# improved_sample-and-hold-cpy.net
KiCad netlist of a schematic drawn in EAGLE
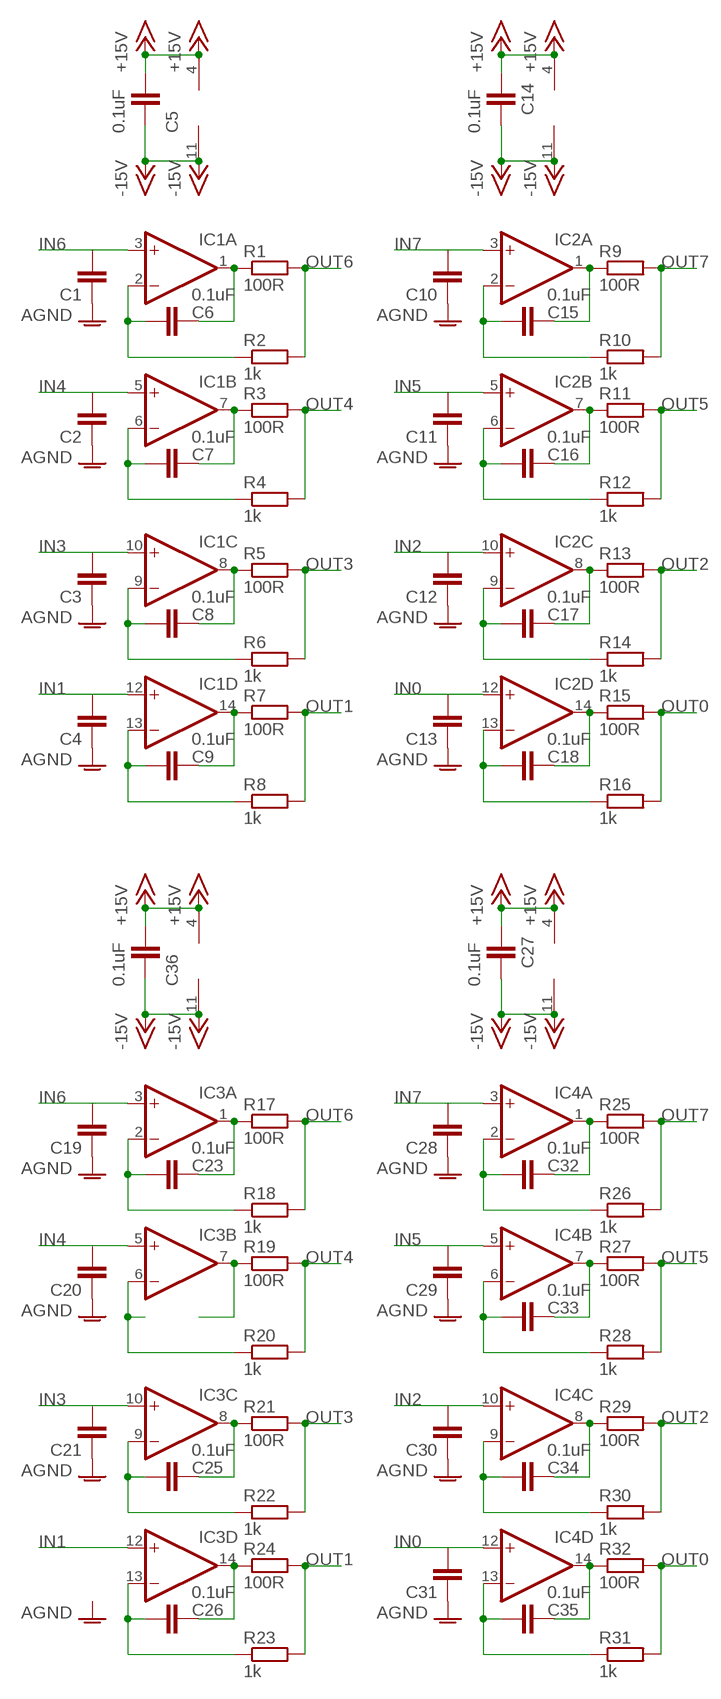
[diagram p0: schematic, sheet 1]

(export (version "E")
  (design (tool "Eeschema 10.0.6"))
  (components
    (comp (ref "C1")
      (value "C-EUC1206")
      (footprint "eagle-import:C1206")
      (libsource (lib "eagle-import") (part "C-EUC1206"))
    )
    (comp (ref "C2")
      (value "C-EUC1206")
      (footprint "eagle-import:C1206")
      (libsource (lib "eagle-import") (part "C-EUC1206"))
    )
    (comp (ref "C3")
      (value "C-EUC1206")
      (footprint "eagle-import:C1206")
      (libsource (lib "eagle-import") (part "C-EUC1206"))
    )
    (comp (ref "C4")
      (value "C-EUC1206")
      (footprint "eagle-import:C1206")
      (libsource (lib "eagle-import") (part "C-EUC1206"))
    )
    (comp (ref "C5")
      (value "0.1uF")
      (footprint "eagle-import:C0603")
      (libsource (lib "eagle-import") (part "C-EUC0603"))
    )
    (comp (ref "C6")
      (value "0.1uF")
      (footprint "eagle-import:C0603")
      (libsource (lib "eagle-import") (part "C-EUC0603"))
    )
    (comp (ref "C7")
      (value "0.1uF")
      (footprint "eagle-import:C0603")
      (libsource (lib "eagle-import") (part "C-EUC0603"))
    )
    (comp (ref "C8")
      (value "0.1uF")
      (footprint "eagle-import:C0603")
      (libsource (lib "eagle-import") (part "C-EUC0603"))
    )
    (comp (ref "C9")
      (value "0.1uF")
      (footprint "eagle-import:C0603")
      (libsource (lib "eagle-import") (part "C-EUC0603"))
    )
    (comp (ref "C10")
      (value "C-EUC1206")
      (footprint "eagle-import:C1206")
      (libsource (lib "eagle-import") (part "C-EUC1206"))
    )
    (comp (ref "C11")
      (value "C-EUC1206")
      (footprint "eagle-import:C1206")
      (libsource (lib "eagle-import") (part "C-EUC1206"))
    )
    (comp (ref "C12")
      (value "C-EUC1206")
      (footprint "eagle-import:C1206")
      (libsource (lib "eagle-import") (part "C-EUC1206"))
    )
    (comp (ref "C13")
      (value "C-EUC1206")
      (footprint "eagle-import:C1206")
      (libsource (lib "eagle-import") (part "C-EUC1206"))
    )
    (comp (ref "C14")
      (value "0.1uF")
      (footprint "eagle-import:C0603")
      (libsource (lib "eagle-import") (part "C-EUC0603"))
    )
    (comp (ref "C15")
      (value "0.1uF")
      (footprint "eagle-import:C0603")
      (libsource (lib "eagle-import") (part "C-EUC0603"))
    )
    (comp (ref "C16")
      (value "0.1uF")
      (footprint "eagle-import:C0603")
      (libsource (lib "eagle-import") (part "C-EUC0603"))
    )
    (comp (ref "C17")
      (value "0.1uF")
      (footprint "eagle-import:C0603")
      (libsource (lib "eagle-import") (part "C-EUC0603"))
    )
    (comp (ref "C18")
      (value "0.1uF")
      (footprint "eagle-import:C0603")
      (libsource (lib "eagle-import") (part "C-EUC0603"))
    )
    (comp (ref "C19")
      (value "C-EUC1206")
      (footprint "eagle-import:C1206")
      (libsource (lib "eagle-import") (part "C-EUC1206"))
    )
    (comp (ref "C20")
      (value "C-EUC1206")
      (footprint "eagle-import:C1206")
      (libsource (lib "eagle-import") (part "C-EUC1206"))
    )
    (comp (ref "C21")
      (value "C-EUC1206")
      (footprint "eagle-import:C1206")
      (libsource (lib "eagle-import") (part "C-EUC1206"))
    )
    (comp (ref "C23")
      (value "0.1uF")
      (footprint "eagle-import:C0603")
      (libsource (lib "eagle-import") (part "C-EUC0603"))
    )
    (comp (ref "C25")
      (value "0.1uF")
      (footprint "eagle-import:C0603")
      (libsource (lib "eagle-import") (part "C-EUC0603"))
    )
    (comp (ref "C26")
      (value "0.1uF")
      (footprint "eagle-import:C0603")
      (libsource (lib "eagle-import") (part "C-EUC0603"))
    )
    (comp (ref "C27")
      (value "0.1uF")
      (footprint "eagle-import:C0603")
      (libsource (lib "eagle-import") (part "C-EUC0603"))
    )
    (comp (ref "C28")
      (value "C-EUC1206")
      (footprint "eagle-import:C1206")
      (libsource (lib "eagle-import") (part "C-EUC1206"))
    )
    (comp (ref "C29")
      (value "C-EUC1206")
      (footprint "eagle-import:C1206")
      (libsource (lib "eagle-import") (part "C-EUC1206"))
    )
    (comp (ref "C30")
      (value "C-EUC1206")
      (footprint "eagle-import:C1206")
      (libsource (lib "eagle-import") (part "C-EUC1206"))
    )
    (comp (ref "C31")
      (value "C-EUC1206")
      (footprint "eagle-import:C1206")
      (libsource (lib "eagle-import") (part "C-EUC1206"))
    )
    (comp (ref "C32")
      (value "0.1uF")
      (footprint "eagle-import:C0603")
      (libsource (lib "eagle-import") (part "C-EUC0603"))
    )
    (comp (ref "C33")
      (value "0.1uF")
      (footprint "eagle-import:C0603")
      (libsource (lib "eagle-import") (part "C-EUC0603"))
    )
    (comp (ref "C34")
      (value "0.1uF")
      (footprint "eagle-import:C0603")
      (libsource (lib "eagle-import") (part "C-EUC0603"))
    )
    (comp (ref "C35")
      (value "0.1uF")
      (footprint "eagle-import:C0603")
      (libsource (lib "eagle-import") (part "C-EUC0603"))
    )
    (comp (ref "C36")
      (value "0.1uF")
      (footprint "eagle-import:C0603")
      (libsource (lib "eagle-import") (part "C-EUC0603"))
    )
    (comp (ref "IC1")
      (value "TL074D")
      (footprint "eagle-import:SO14")
      (libsource (lib "eagle-import") (part "TL074D"))
    )
    (comp (ref "IC2")
      (value "TL074D")
      (footprint "eagle-import:SO14")
      (libsource (lib "eagle-import") (part "TL074D"))
    )
    (comp (ref "IC3")
      (value "TL074D")
      (footprint "eagle-import:SO14")
      (libsource (lib "eagle-import") (part "TL074D"))
    )
    (comp (ref "IC4")
      (value "TL074D")
      (footprint "eagle-import:SO14")
      (libsource (lib "eagle-import") (part "TL074D"))
    )
    (comp (ref "R1")
      (value "100R")
      (footprint "eagle-import:R0603")
      (libsource (lib "eagle-import") (part "R-EU_R0603"))
    )
    (comp (ref "R2")
      (value "1k")
      (footprint "eagle-import:R0603")
      (libsource (lib "eagle-import") (part "R-EU_R0603"))
    )
    (comp (ref "R3")
      (value "100R")
      (footprint "eagle-import:R0603")
      (libsource (lib "eagle-import") (part "R-EU_R0603"))
    )
    (comp (ref "R4")
      (value "1k")
      (footprint "eagle-import:R0603")
      (libsource (lib "eagle-import") (part "R-EU_R0603"))
    )
    (comp (ref "R5")
      (value "100R")
      (footprint "eagle-import:R0603")
      (libsource (lib "eagle-import") (part "R-EU_R0603"))
    )
    (comp (ref "R6")
      (value "1k")
      (footprint "eagle-import:R0603")
      (libsource (lib "eagle-import") (part "R-EU_R0603"))
    )
    (comp (ref "R7")
      (value "100R")
      (footprint "eagle-import:R0603")
      (libsource (lib "eagle-import") (part "R-EU_R0603"))
    )
    (comp (ref "R8")
      (value "1k")
      (footprint "eagle-import:R0603")
      (libsource (lib "eagle-import") (part "R-EU_R0603"))
    )
    (comp (ref "R9")
      (value "100R")
      (footprint "eagle-import:R0603")
      (libsource (lib "eagle-import") (part "R-EU_R0603"))
    )
    (comp (ref "R10")
      (value "1k")
      (footprint "eagle-import:R0603")
      (libsource (lib "eagle-import") (part "R-EU_R0603"))
    )
    (comp (ref "R11")
      (value "100R")
      (footprint "eagle-import:R0603")
      (libsource (lib "eagle-import") (part "R-EU_R0603"))
    )
    (comp (ref "R12")
      (value "1k")
      (footprint "eagle-import:R0603")
      (libsource (lib "eagle-import") (part "R-EU_R0603"))
    )
    (comp (ref "R13")
      (value "100R")
      (footprint "eagle-import:R0603")
      (libsource (lib "eagle-import") (part "R-EU_R0603"))
    )
    (comp (ref "R14")
      (value "1k")
      (footprint "eagle-import:R0603")
      (libsource (lib "eagle-import") (part "R-EU_R0603"))
    )
    (comp (ref "R15")
      (value "100R")
      (footprint "eagle-import:R0603")
      (libsource (lib "eagle-import") (part "R-EU_R0603"))
    )
    (comp (ref "R16")
      (value "1k")
      (footprint "eagle-import:R0603")
      (libsource (lib "eagle-import") (part "R-EU_R0603"))
    )
    (comp (ref "R17")
      (value "100R")
      (footprint "eagle-import:R0603")
      (libsource (lib "eagle-import") (part "R-EU_R0603"))
    )
    (comp (ref "R18")
      (value "1k")
      (footprint "eagle-import:R0603")
      (libsource (lib "eagle-import") (part "R-EU_R0603"))
    )
    (comp (ref "R19")
      (value "100R")
      (footprint "eagle-import:R0603")
      (libsource (lib "eagle-import") (part "R-EU_R0603"))
    )
    (comp (ref "R20")
      (value "1k")
      (footprint "eagle-import:R0603")
      (libsource (lib "eagle-import") (part "R-EU_R0603"))
    )
    (comp (ref "R21")
      (value "100R")
      (footprint "eagle-import:R0603")
      (libsource (lib "eagle-import") (part "R-EU_R0603"))
    )
    (comp (ref "R22")
      (value "1k")
      (footprint "eagle-import:R0603")
      (libsource (lib "eagle-import") (part "R-EU_R0603"))
    )
    (comp (ref "R23")
      (value "1k")
      (footprint "eagle-import:R0603")
      (libsource (lib "eagle-import") (part "R-EU_R0603"))
    )
    (comp (ref "R24")
      (value "100R")
      (footprint "eagle-import:R0603")
      (libsource (lib "eagle-import") (part "R-EU_R0603"))
    )
    (comp (ref "R25")
      (value "100R")
      (footprint "eagle-import:R0603")
      (libsource (lib "eagle-import") (part "R-EU_R0603"))
    )
    (comp (ref "R26")
      (value "1k")
      (footprint "eagle-import:R0603")
      (libsource (lib "eagle-import") (part "R-EU_R0603"))
    )
    (comp (ref "R27")
      (value "100R")
      (footprint "eagle-import:R0603")
      (libsource (lib "eagle-import") (part "R-EU_R0603"))
    )
    (comp (ref "R28")
      (value "1k")
      (footprint "eagle-import:R0603")
      (libsource (lib "eagle-import") (part "R-EU_R0603"))
    )
    (comp (ref "R29")
      (value "100R")
      (footprint "eagle-import:R0603")
      (libsource (lib "eagle-import") (part "R-EU_R0603"))
    )
    (comp (ref "R30")
      (value "1k")
      (footprint "eagle-import:R0603")
      (libsource (lib "eagle-import") (part "R-EU_R0603"))
    )
    (comp (ref "R31")
      (value "1k")
      (footprint "eagle-import:R0603")
      (libsource (lib "eagle-import") (part "R-EU_R0603"))
    )
    (comp (ref "R32")
      (value "100R")
      (footprint "eagle-import:R0603")
      (libsource (lib "eagle-import") (part "R-EU_R0603"))
    )
  )
  (nets
    (net (code "1") (name "+15V") (class "Default")
      (node (ref "C14") (pin "1") (pinfunction "1_1") (pintype "passive"))
      (node (ref "C27") (pin "1") (pinfunction "1_1") (pintype "passive"))
      (node (ref "C36") (pin "1") (pinfunction "1_1") (pintype "passive"))
      (node (ref "C5") (pin "1") (pinfunction "1_1") (pintype "passive"))
      (node (ref "IC1") (pin "4") (pinfunction "V+_4") (pintype "power_in"))
      (node (ref "IC2") (pin "4") (pinfunction "V+_4") (pintype "power_in"))
      (node (ref "IC3") (pin "4") (pinfunction "V+_4") (pintype "power_in"))
      (node (ref "IC4") (pin "4") (pinfunction "V+_4") (pintype "power_in"))
    )
    (net (code "2") (name "-15V") (class "Default")
      (node (ref "C14") (pin "2") (pinfunction "2_2") (pintype "passive"))
      (node (ref "C27") (pin "2") (pinfunction "2_2") (pintype "passive"))
      (node (ref "C36") (pin "2") (pinfunction "2_2") (pintype "passive"))
      (node (ref "C5") (pin "2") (pinfunction "2_2") (pintype "passive"))
      (node (ref "IC1") (pin "11") (pinfunction "V-_11") (pintype "power_in"))
      (node (ref "IC2") (pin "11") (pinfunction "V-_11") (pintype "power_in"))
      (node (ref "IC3") (pin "11") (pinfunction "V-_11") (pintype "power_in"))
      (node (ref "IC4") (pin "11") (pinfunction "V-_11") (pintype "power_in"))
    )
    (net (code "3") (name "/IN0") (class "Default")
      (node (ref "C13") (pin "2") (pinfunction "2_2") (pintype "passive"))
      (node (ref "C31") (pin "2") (pinfunction "2_2") (pintype "passive"))
      (node (ref "IC2") (pin "12") (pinfunction "+IN_12") (pintype "input"))
      (node (ref "IC4") (pin "12") (pinfunction "+IN_12") (pintype "input"))
    )
    (net (code "4") (name "/IN1") (class "Default")
      (node (ref "C4") (pin "2") (pinfunction "2_2") (pintype "passive"))
      (node (ref "IC1") (pin "12") (pinfunction "+IN_12") (pintype "input"))
      (node (ref "IC3") (pin "12") (pinfunction "+IN_12") (pintype "input"))
    )
    (net (code "5") (name "/IN2") (class "Default")
      (node (ref "C12") (pin "2") (pinfunction "2_2") (pintype "passive"))
      (node (ref "C30") (pin "2") (pinfunction "2_2") (pintype "passive"))
      (node (ref "IC2") (pin "10") (pinfunction "+IN_10") (pintype "input"))
      (node (ref "IC4") (pin "10") (pinfunction "+IN_10") (pintype "input"))
    )
    (net (code "6") (name "/IN3") (class "Default")
      (node (ref "C21") (pin "2") (pinfunction "2_2") (pintype "passive"))
      (node (ref "C3") (pin "2") (pinfunction "2_2") (pintype "passive"))
      (node (ref "IC1") (pin "10") (pinfunction "+IN_10") (pintype "input"))
      (node (ref "IC3") (pin "10") (pinfunction "+IN_10") (pintype "input"))
    )
    (net (code "7") (name "/IN4") (class "Default")
      (node (ref "C2") (pin "2") (pinfunction "2_2") (pintype "passive"))
      (node (ref "C20") (pin "2") (pinfunction "2_2") (pintype "passive"))
      (node (ref "IC1") (pin "5") (pinfunction "+IN_5") (pintype "input"))
      (node (ref "IC3") (pin "5") (pinfunction "+IN_5") (pintype "input"))
    )
    (net (code "8") (name "/IN5") (class "Default")
      (node (ref "C11") (pin "2") (pinfunction "2_2") (pintype "passive"))
      (node (ref "C29") (pin "2") (pinfunction "2_2") (pintype "passive"))
      (node (ref "IC2") (pin "5") (pinfunction "+IN_5") (pintype "input"))
      (node (ref "IC4") (pin "5") (pinfunction "+IN_5") (pintype "input"))
    )
    (net (code "9") (name "/IN6") (class "Default")
      (node (ref "C1") (pin "2") (pinfunction "2_2") (pintype "passive"))
      (node (ref "C19") (pin "2") (pinfunction "2_2") (pintype "passive"))
      (node (ref "IC1") (pin "3") (pinfunction "+IN_3") (pintype "input"))
      (node (ref "IC3") (pin "3") (pinfunction "+IN_3") (pintype "input"))
    )
    (net (code "10") (name "/IN7") (class "Default")
      (node (ref "C10") (pin "2") (pinfunction "2_2") (pintype "passive"))
      (node (ref "C28") (pin "2") (pinfunction "2_2") (pintype "passive"))
      (node (ref "IC2") (pin "3") (pinfunction "+IN_3") (pintype "input"))
      (node (ref "IC4") (pin "3") (pinfunction "+IN_3") (pintype "input"))
    )
    (net (code "11") (name "/OUT0") (class "Default")
      (node (ref "R15") (pin "2") (pinfunction "2_2") (pintype "passive"))
      (node (ref "R16") (pin "2") (pinfunction "2_2") (pintype "passive"))
      (node (ref "R31") (pin "2") (pinfunction "2_2") (pintype "passive"))
      (node (ref "R32") (pin "2") (pinfunction "2_2") (pintype "passive"))
    )
    (net (code "12") (name "/OUT1") (class "Default")
      (node (ref "R23") (pin "2") (pinfunction "2_2") (pintype "passive"))
      (node (ref "R24") (pin "2") (pinfunction "2_2") (pintype "passive"))
      (node (ref "R7") (pin "2") (pinfunction "2_2") (pintype "passive"))
      (node (ref "R8") (pin "2") (pinfunction "2_2") (pintype "passive"))
    )
    (net (code "13") (name "/OUT2") (class "Default")
      (node (ref "R13") (pin "2") (pinfunction "2_2") (pintype "passive"))
      (node (ref "R14") (pin "2") (pinfunction "2_2") (pintype "passive"))
      (node (ref "R29") (pin "2") (pinfunction "2_2") (pintype "passive"))
      (node (ref "R30") (pin "2") (pinfunction "2_2") (pintype "passive"))
    )
    (net (code "14") (name "/OUT3") (class "Default")
      (node (ref "R21") (pin "2") (pinfunction "2_2") (pintype "passive"))
      (node (ref "R22") (pin "2") (pinfunction "2_2") (pintype "passive"))
      (node (ref "R5") (pin "2") (pinfunction "2_2") (pintype "passive"))
      (node (ref "R6") (pin "2") (pinfunction "2_2") (pintype "passive"))
    )
    (net (code "15") (name "/OUT4") (class "Default")
      (node (ref "R19") (pin "2") (pinfunction "2_2") (pintype "passive"))
      (node (ref "R20") (pin "2") (pinfunction "2_2") (pintype "passive"))
      (node (ref "R3") (pin "2") (pinfunction "2_2") (pintype "passive"))
      (node (ref "R4") (pin "2") (pinfunction "2_2") (pintype "passive"))
    )
    (net (code "16") (name "/OUT5") (class "Default")
      (node (ref "R11") (pin "2") (pinfunction "2_2") (pintype "passive"))
      (node (ref "R12") (pin "2") (pinfunction "2_2") (pintype "passive"))
      (node (ref "R27") (pin "2") (pinfunction "2_2") (pintype "passive"))
      (node (ref "R28") (pin "2") (pinfunction "2_2") (pintype "passive"))
    )
    (net (code "17") (name "/OUT6") (class "Default")
      (node (ref "R1") (pin "2") (pinfunction "2_2") (pintype "passive"))
      (node (ref "R17") (pin "2") (pinfunction "2_2") (pintype "passive"))
      (node (ref "R18") (pin "2") (pinfunction "2_2") (pintype "passive"))
      (node (ref "R2") (pin "2") (pinfunction "2_2") (pintype "passive"))
    )
    (net (code "18") (name "/OUT7") (class "Default")
      (node (ref "R10") (pin "2") (pinfunction "2_2") (pintype "passive"))
      (node (ref "R25") (pin "2") (pinfunction "2_2") (pintype "passive"))
      (node (ref "R26") (pin "2") (pinfunction "2_2") (pintype "passive"))
      (node (ref "R9") (pin "2") (pinfunction "2_2") (pintype "passive"))
    )
    (net (code "19") (name "AGND") (class "Default")
      (node (ref "C1") (pin "1") (pinfunction "1_1") (pintype "passive"))
      (node (ref "C10") (pin "1") (pinfunction "1_1") (pintype "passive"))
      (node (ref "C11") (pin "1") (pinfunction "1_1") (pintype "passive"))
      (node (ref "C12") (pin "1") (pinfunction "1_1") (pintype "passive"))
      (node (ref "C13") (pin "1") (pinfunction "1_1") (pintype "passive"))
      (node (ref "C19") (pin "1") (pinfunction "1_1") (pintype "passive"))
      (node (ref "C2") (pin "1") (pinfunction "1_1") (pintype "passive"))
      (node (ref "C20") (pin "1") (pinfunction "1_1") (pintype "passive"))
      (node (ref "C21") (pin "1") (pinfunction "1_1") (pintype "passive"))
      (node (ref "C28") (pin "1") (pinfunction "1_1") (pintype "passive"))
      (node (ref "C29") (pin "1") (pinfunction "1_1") (pintype "passive"))
      (node (ref "C3") (pin "1") (pinfunction "1_1") (pintype "passive"))
      (node (ref "C30") (pin "1") (pinfunction "1_1") (pintype "passive"))
      (node (ref "C31") (pin "1") (pinfunction "1_1") (pintype "passive"))
      (node (ref "C4") (pin "1") (pinfunction "1_1") (pintype "passive"))
    )
    (net (code "20") (name "Net-(IC1A--IN)") (class "Default")
      (node (ref "C6") (pin "2") (pinfunction "2_2") (pintype "passive"))
      (node (ref "IC1") (pin "2") (pinfunction "-IN_2") (pintype "input"))
      (node (ref "R2") (pin "1") (pinfunction "1_1") (pintype "passive"))
    )
    (net (code "21") (name "Net-(IC1A-OUT)") (class "Default")
      (node (ref "C6") (pin "1") (pinfunction "1_1") (pintype "passive"))
      (node (ref "IC1") (pin "1") (pinfunction "OUT_1") (pintype "output"))
      (node (ref "R1") (pin "1") (pinfunction "1_1") (pintype "passive"))
    )
    (net (code "22") (name "Net-(IC1B--IN)") (class "Default")
      (node (ref "C7") (pin "2") (pinfunction "2_2") (pintype "passive"))
      (node (ref "IC1") (pin "6") (pinfunction "-IN_6") (pintype "input"))
      (node (ref "R4") (pin "1") (pinfunction "1_1") (pintype "passive"))
    )
    (net (code "23") (name "Net-(IC1B-OUT)") (class "Default")
      (node (ref "C7") (pin "1") (pinfunction "1_1") (pintype "passive"))
      (node (ref "IC1") (pin "7") (pinfunction "OUT_7") (pintype "output"))
      (node (ref "R3") (pin "1") (pinfunction "1_1") (pintype "passive"))
    )
    (net (code "24") (name "Net-(IC1C--IN)") (class "Default")
      (node (ref "C8") (pin "2") (pinfunction "2_2") (pintype "passive"))
      (node (ref "IC1") (pin "9") (pinfunction "-IN_9") (pintype "input"))
      (node (ref "R6") (pin "1") (pinfunction "1_1") (pintype "passive"))
    )
    (net (code "25") (name "Net-(IC1C-OUT)") (class "Default")
      (node (ref "C8") (pin "1") (pinfunction "1_1") (pintype "passive"))
      (node (ref "IC1") (pin "8") (pinfunction "OUT_8") (pintype "output"))
      (node (ref "R5") (pin "1") (pinfunction "1_1") (pintype "passive"))
    )
    (net (code "26") (name "Net-(IC1D--IN)") (class "Default")
      (node (ref "C9") (pin "2") (pinfunction "2_2") (pintype "passive"))
      (node (ref "IC1") (pin "13") (pinfunction "-IN_13") (pintype "input"))
      (node (ref "R8") (pin "1") (pinfunction "1_1") (pintype "passive"))
    )
    (net (code "27") (name "Net-(IC1D-OUT)") (class "Default")
      (node (ref "C9") (pin "1") (pinfunction "1_1") (pintype "passive"))
      (node (ref "IC1") (pin "14") (pinfunction "OUT_14") (pintype "output"))
      (node (ref "R7") (pin "1") (pinfunction "1_1") (pintype "passive"))
    )
    (net (code "28") (name "Net-(IC2A--IN)") (class "Default")
      (node (ref "C15") (pin "2") (pinfunction "2_2") (pintype "passive"))
      (node (ref "IC2") (pin "2") (pinfunction "-IN_2") (pintype "input"))
      (node (ref "R10") (pin "1") (pinfunction "1_1") (pintype "passive"))
    )
    (net (code "29") (name "Net-(IC2A-OUT)") (class "Default")
      (node (ref "C15") (pin "1") (pinfunction "1_1") (pintype "passive"))
      (node (ref "IC2") (pin "1") (pinfunction "OUT_1") (pintype "output"))
      (node (ref "R9") (pin "1") (pinfunction "1_1") (pintype "passive"))
    )
    (net (code "30") (name "Net-(IC2B--IN)") (class "Default")
      (node (ref "C16") (pin "2") (pinfunction "2_2") (pintype "passive"))
      (node (ref "IC2") (pin "6") (pinfunction "-IN_6") (pintype "input"))
      (node (ref "R12") (pin "1") (pinfunction "1_1") (pintype "passive"))
    )
    (net (code "31") (name "Net-(IC2B-OUT)") (class "Default")
      (node (ref "C16") (pin "1") (pinfunction "1_1") (pintype "passive"))
      (node (ref "IC2") (pin "7") (pinfunction "OUT_7") (pintype "output"))
      (node (ref "R11") (pin "1") (pinfunction "1_1") (pintype "passive"))
    )
    (net (code "32") (name "Net-(IC2C--IN)") (class "Default")
      (node (ref "C17") (pin "2") (pinfunction "2_2") (pintype "passive"))
      (node (ref "IC2") (pin "9") (pinfunction "-IN_9") (pintype "input"))
      (node (ref "R14") (pin "1") (pinfunction "1_1") (pintype "passive"))
    )
    (net (code "33") (name "Net-(IC2C-OUT)") (class "Default")
      (node (ref "C17") (pin "1") (pinfunction "1_1") (pintype "passive"))
      (node (ref "IC2") (pin "8") (pinfunction "OUT_8") (pintype "output"))
      (node (ref "R13") (pin "1") (pinfunction "1_1") (pintype "passive"))
    )
    (net (code "34") (name "Net-(IC2D--IN)") (class "Default")
      (node (ref "C18") (pin "2") (pinfunction "2_2") (pintype "passive"))
      (node (ref "IC2") (pin "13") (pinfunction "-IN_13") (pintype "input"))
      (node (ref "R16") (pin "1") (pinfunction "1_1") (pintype "passive"))
    )
    (net (code "35") (name "Net-(IC2D-OUT)") (class "Default")
      (node (ref "C18") (pin "1") (pinfunction "1_1") (pintype "passive"))
      (node (ref "IC2") (pin "14") (pinfunction "OUT_14") (pintype "output"))
      (node (ref "R15") (pin "1") (pinfunction "1_1") (pintype "passive"))
    )
    (net (code "36") (name "Net-(IC3A--IN)") (class "Default")
      (node (ref "C23") (pin "2") (pinfunction "2_2") (pintype "passive"))
      (node (ref "IC3") (pin "2") (pinfunction "-IN_2") (pintype "input"))
      (node (ref "R18") (pin "1") (pinfunction "1_1") (pintype "passive"))
    )
    (net (code "37") (name "Net-(IC3A-OUT)") (class "Default")
      (node (ref "C23") (pin "1") (pinfunction "1_1") (pintype "passive"))
      (node (ref "IC3") (pin "1") (pinfunction "OUT_1") (pintype "output"))
      (node (ref "R17") (pin "1") (pinfunction "1_1") (pintype "passive"))
    )
    (net (code "38") (name "Net-(IC3B--IN)") (class "Default")
      (node (ref "IC3") (pin "6") (pinfunction "-IN_6") (pintype "input"))
      (node (ref "R20") (pin "1") (pinfunction "1_1") (pintype "passive"))
    )
    (net (code "39") (name "Net-(IC3B-OUT)") (class "Default")
      (node (ref "IC3") (pin "7") (pinfunction "OUT_7") (pintype "output"))
      (node (ref "R19") (pin "1") (pinfunction "1_1") (pintype "passive"))
    )
    (net (code "40") (name "Net-(IC3C--IN)") (class "Default")
      (node (ref "C25") (pin "2") (pinfunction "2_2") (pintype "passive"))
      (node (ref "IC3") (pin "9") (pinfunction "-IN_9") (pintype "input"))
      (node (ref "R22") (pin "1") (pinfunction "1_1") (pintype "passive"))
    )
    (net (code "41") (name "Net-(IC3C-OUT)") (class "Default")
      (node (ref "C25") (pin "1") (pinfunction "1_1") (pintype "passive"))
      (node (ref "IC3") (pin "8") (pinfunction "OUT_8") (pintype "output"))
      (node (ref "R21") (pin "1") (pinfunction "1_1") (pintype "passive"))
    )
    (net (code "42") (name "Net-(IC3D--IN)") (class "Default")
      (node (ref "C26") (pin "2") (pinfunction "2_2") (pintype "passive"))
      (node (ref "IC3") (pin "13") (pinfunction "-IN_13") (pintype "input"))
      (node (ref "R23") (pin "1") (pinfunction "1_1") (pintype "passive"))
    )
    (net (code "43") (name "Net-(IC3D-OUT)") (class "Default")
      (node (ref "C26") (pin "1") (pinfunction "1_1") (pintype "passive"))
      (node (ref "IC3") (pin "14") (pinfunction "OUT_14") (pintype "output"))
      (node (ref "R24") (pin "1") (pinfunction "1_1") (pintype "passive"))
    )
    (net (code "44") (name "Net-(IC4A--IN)") (class "Default")
      (node (ref "C32") (pin "2") (pinfunction "2_2") (pintype "passive"))
      (node (ref "IC4") (pin "2") (pinfunction "-IN_2") (pintype "input"))
      (node (ref "R26") (pin "1") (pinfunction "1_1") (pintype "passive"))
    )
    (net (code "45") (name "Net-(IC4A-OUT)") (class "Default")
      (node (ref "C32") (pin "1") (pinfunction "1_1") (pintype "passive"))
      (node (ref "IC4") (pin "1") (pinfunction "OUT_1") (pintype "output"))
      (node (ref "R25") (pin "1") (pinfunction "1_1") (pintype "passive"))
    )
    (net (code "46") (name "Net-(IC4B--IN)") (class "Default")
      (node (ref "C33") (pin "2") (pinfunction "2_2") (pintype "passive"))
      (node (ref "IC4") (pin "6") (pinfunction "-IN_6") (pintype "input"))
      (node (ref "R28") (pin "1") (pinfunction "1_1") (pintype "passive"))
    )
    (net (code "47") (name "Net-(IC4B-OUT)") (class "Default")
      (node (ref "C33") (pin "1") (pinfunction "1_1") (pintype "passive"))
      (node (ref "IC4") (pin "7") (pinfunction "OUT_7") (pintype "output"))
      (node (ref "R27") (pin "1") (pinfunction "1_1") (pintype "passive"))
    )
    (net (code "48") (name "Net-(IC4C--IN)") (class "Default")
      (node (ref "C34") (pin "2") (pinfunction "2_2") (pintype "passive"))
      (node (ref "IC4") (pin "9") (pinfunction "-IN_9") (pintype "input"))
      (node (ref "R30") (pin "1") (pinfunction "1_1") (pintype "passive"))
    )
    (net (code "49") (name "Net-(IC4C-OUT)") (class "Default")
      (node (ref "C34") (pin "1") (pinfunction "1_1") (pintype "passive"))
      (node (ref "IC4") (pin "8") (pinfunction "OUT_8") (pintype "output"))
      (node (ref "R29") (pin "1") (pinfunction "1_1") (pintype "passive"))
    )
    (net (code "50") (name "Net-(IC4D--IN)") (class "Default")
      (node (ref "C35") (pin "2") (pinfunction "2_2") (pintype "passive"))
      (node (ref "IC4") (pin "13") (pinfunction "-IN_13") (pintype "input"))
      (node (ref "R31") (pin "1") (pinfunction "1_1") (pintype "passive"))
    )
    (net (code "51") (name "Net-(IC4D-OUT)") (class "Default")
      (node (ref "C35") (pin "1") (pinfunction "1_1") (pintype "passive"))
      (node (ref "IC4") (pin "14") (pinfunction "OUT_14") (pintype "output"))
      (node (ref "R32") (pin "1") (pinfunction "1_1") (pintype "passive"))
    )
  )
)
